# pic.net
KiCad netlist of a schematic drawn in Altium Designer
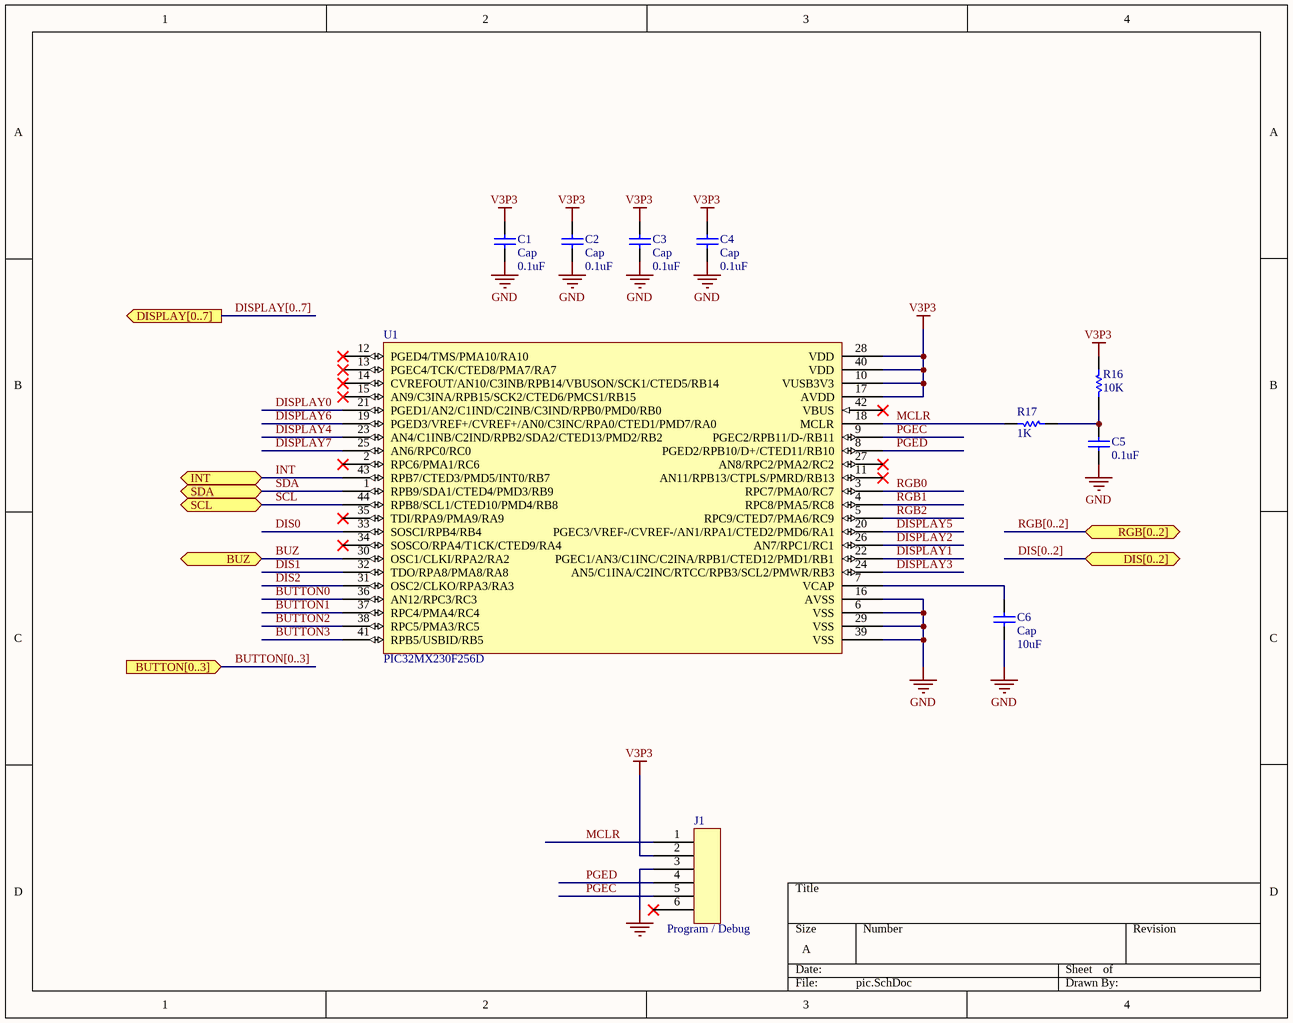
[diagram p0: pic.SchDoc]

(export (version "E")
  (design (tool "Eeschema 10.0.6"))
  (components
    (comp (ref "C1")
      (value "Cap")
      (footprint "Capacitor")
      (description "Capacitor")
      (fields (field (name "ALTIUM_VALUE") "0.1uF") (field (name "PUBLISHER") "Altium Limited"))
      (libsource (lib "libProject") (part "Capacitor"))
    )
    (comp (ref "C2")
      (value "Cap")
      (footprint "Capacitor")
      (description "Capacitor")
      (fields (field (name "ALTIUM_VALUE") "0.1uF") (field (name "PUBLISHER") "Altium Limited"))
      (libsource (lib "libProject") (part "Capacitor"))
    )
    (comp (ref "C3")
      (value "Cap")
      (footprint "Capacitor")
      (description "Capacitor")
      (fields (field (name "ALTIUM_VALUE") "0.1uF") (field (name "PUBLISHER") "Altium Limited"))
      (libsource (lib "libProject") (part "Capacitor"))
    )
    (comp (ref "C4")
      (value "Cap")
      (footprint "Capacitor")
      (description "Capacitor")
      (fields (field (name "ALTIUM_VALUE") "0.1uF") (field (name "PUBLISHER") "Altium Limited"))
      (libsource (lib "libProject") (part "Capacitor"))
    )
    (comp (ref "C5")
      (value "0.1uF")
      (footprint "Capacitor")
      (description "Capacitor")
      (fields (field (name "Comment") "Cap") (field (name "PUBLISHER") "Altium Limited"))
      (libsource (lib "libProject") (part "Capacitor"))
    )
    (comp (ref "C6")
      (value "Cap")
      (footprint "Capacitor")
      (description "Capacitor")
      (fields (field (name "ALTIUM_VALUE") "10uF") (field (name "PUBLISHER") "Altium Limited"))
      (libsource (lib "Miscellaneous Devices") (part "Cap"))
    )
    (comp (ref "J1") (value "Program / Debug") (footprint "ICSP") (libsource (lib "TP2") (part "CON6")))
    (comp (ref "R16")
      (value "10K")
      (footprint "RESISTANCE")
      (description "Resistor")
      (fields (field (name "PUBLISHER") "Altium Limited"))
      (libsource (lib "Miscellaneous Devices") (part "Res1"))
    )
    (comp (ref "R17")
      (value "1K")
      (footprint "RESISTANCE")
      (description "Resistor")
      (fields (field (name "Comment") "10K") (field (name "PUBLISHER") "Altium Limited"))
      (libsource (lib "Miscellaneous Devices") (part "Res1"))
    )
    (comp (ref "U1")
      (value "PIC32MX230F256D")
      (footprint "PIC32")
      (libsource (lib "libProject") (part "PIC32MX230F256D"))
    )
  )
  (nets
    (net (code "1") (name "/BUTTON0") (class "Default")
      (node (ref "U1") (pin "36") (pinfunction "AN12/RPC3/RC3_36") (pintype "bidirectional"))
    )
    (net (code "2") (name "/BUTTON1") (class "Default")
      (node (ref "U1") (pin "37") (pinfunction "RPC4/PMA4/RC4_37") (pintype "bidirectional"))
    )
    (net (code "3") (name "/BUTTON2") (class "Default")
      (node (ref "U1") (pin "38") (pinfunction "RPC5/PMA3/RC5_38") (pintype "bidirectional"))
    )
    (net (code "4") (name "/BUTTON3") (class "Default")
      (node (ref "U1") (pin "41") (pinfunction "RPB5/USBID/RB5_41") (pintype "bidirectional"))
    )
    (net (code "6") (name "/BUZ") (class "Default")
      (node (ref "U1") (pin "30") (pinfunction "OSC1/CLKI/RPA2/RA2_30") (pintype "bidirectional"))
    )
    (net (code "7") (name "/DIS0") (class "Default")
      (node (ref "U1") (pin "33") (pinfunction "SOSCI/RPB4/RB4_33") (pintype "bidirectional"))
    )
    (net (code "8") (name "/DIS1") (class "Default")
      (node (ref "U1") (pin "32") (pinfunction "TDO/RPA8/PMA8/RA8_32") (pintype "bidirectional"))
    )
    (net (code "9") (name "/DIS2") (class "Default")
      (node (ref "U1") (pin "31") (pinfunction "OSC2/CLKO/RPA3/RA3_31") (pintype "bidirectional"))
    )
    (net (code "10") (name "/DISPLAY0") (class "Default")
      (node (ref "U1") (pin "21") (pinfunction "PGED1/AN2/C1IND/C2INB/C3IND/RPB0/PMD0/RB0_21") (pintype "bidirectional"))
    )
    (net (code "11") (name "/DISPLAY1") (class "Default")
      (node (ref "U1") (pin "22") (pinfunction "PGEC1/AN3/C1INC/C2INA/RPB1/CTED12/PMD1/RB1_22") (pintype "bidirectional"))
    )
    (net (code "12") (name "/DISPLAY2") (class "Default")
      (node (ref "U1") (pin "26") (pinfunction "AN7/RPC1/RC1_26") (pintype "bidirectional"))
    )
    (net (code "13") (name "/DISPLAY3") (class "Default")
      (node (ref "U1") (pin "24") (pinfunction "AN5/C1INA/C2INC/RTCC/RPB3/SCL2/PMWR/RB3_24") (pintype "bidirectional"))
    )
    (net (code "14") (name "/DISPLAY4") (class "Default")
      (node (ref "U1") (pin "23") (pinfunction "AN4/C1INB/C2IND/RPB2/SDA2/CTED13/PMD2/RB2_23") (pintype "bidirectional"))
    )
    (net (code "15") (name "/DISPLAY5") (class "Default")
      (node (ref "U1") (pin "20") (pinfunction "PGEC3/VREF-/CVREF-/AN1/RPA1/CTED2/PMD6/RA1_20") (pintype "bidirectional"))
    )
    (net (code "16") (name "/DISPLAY6") (class "Default")
      (node (ref "U1") (pin "19") (pinfunction "PGED3/VREF+/CVREF+/AN0/C3INC/RPA0/CTED1/PMD7/RA0_19") (pintype "bidirectional"))
    )
    (net (code "17") (name "/DISPLAY7") (class "Default")
      (node (ref "U1") (pin "25") (pinfunction "AN6/RPC0/RC0_25") (pintype "bidirectional"))
    )
    (net (code "20") (name "/INT") (class "Default")
      (node (ref "U1") (pin "43") (pinfunction "RPB7/CTED3/PMD5/INT0/RB7_43") (pintype "bidirectional"))
    )
    (net (code "21") (name "/MCLR") (class "Default")
      (node (ref "J1") (pin "1") (pinfunction "1_1") (pintype "passive"))
      (node (ref "R17") (pin "1") (pinfunction "1_1") (pintype "passive"))
      (node (ref "U1") (pin "18") (pinfunction "MCLR_18") (pintype "power_in"))
    )
    (net (code "22") (name "/PGEC") (class "Default")
      (node (ref "J1") (pin "5") (pinfunction "5_5") (pintype "passive"))
      (node (ref "U1") (pin "9") (pinfunction "PGEC2/RPB11/D-/RB11_9") (pintype "bidirectional"))
    )
    (net (code "23") (name "/PGED") (class "Default")
      (node (ref "J1") (pin "4") (pinfunction "4_4") (pintype "passive"))
      (node (ref "U1") (pin "8") (pinfunction "PGED2/RPB10/D+/CTED11/RB10_8") (pintype "bidirectional"))
    )
    (net (code "24") (name "/RGB0") (class "Default")
      (node (ref "U1") (pin "3") (pinfunction "RPC7/PMA0/RC7_3") (pintype "bidirectional"))
    )
    (net (code "25") (name "/RGB1") (class "Default")
      (node (ref "U1") (pin "4") (pinfunction "RPC8/PMA5/RC8_4") (pintype "bidirectional"))
    )
    (net (code "26") (name "/RGB2") (class "Default")
      (node (ref "U1") (pin "5") (pinfunction "RPC9/CTED7/PMA6/RC9_5") (pintype "bidirectional"))
    )
    (net (code "28") (name "/SCL") (class "Default")
      (node (ref "U1") (pin "44") (pinfunction "RPB8/SCL1/CTED10/PMD4/RB8_44") (pintype "bidirectional"))
    )
    (net (code "29") (name "/SDA") (class "Default")
      (node (ref "U1") (pin "1") (pinfunction "RPB9/SDA1/CTED4/PMD3/RB9_1") (pintype "bidirectional"))
    )
    (net (code "30") (name "GND") (class "Default")
      (node (ref "C1") (pin "1") (pinfunction "1_1") (pintype "passive"))
      (node (ref "C2") (pin "1") (pinfunction "1_1") (pintype "passive"))
      (node (ref "C3") (pin "1") (pinfunction "1_1") (pintype "passive"))
      (node (ref "C4") (pin "1") (pinfunction "1_1") (pintype "passive"))
      (node (ref "C5") (pin "1") (pinfunction "1_1") (pintype "passive"))
      (node (ref "C6") (pin "1") (pinfunction "1_1") (pintype "passive"))
      (node (ref "J1") (pin "3") (pinfunction "3_3") (pintype "passive"))
      (node (ref "U1") (pin "16") (pinfunction "AVSS_16") (pintype "power_in"))
      (node (ref "U1") (pin "29") (pinfunction "VSS_29") (pintype "power_in"))
      (node (ref "U1") (pin "39") (pinfunction "VSS_39") (pintype "power_in"))
      (node (ref "U1") (pin "6") (pinfunction "VSS_6") (pintype "power_in"))
    )
    (net (code "31") (name "Net-(C5-Pad2)") (class "Default")
      (node (ref "C5") (pin "2") (pinfunction "2_2") (pintype "passive"))
      (node (ref "R16") (pin "1") (pinfunction "1_1") (pintype "passive"))
      (node (ref "R17") (pin "2") (pinfunction "2_2") (pintype "passive"))
    )
    (net (code "32") (name "Net-(U1-VCAP)") (class "Default")
      (node (ref "C6") (pin "2") (pinfunction "2_2") (pintype "passive"))
      (node (ref "U1") (pin "7") (pinfunction "VCAP_7") (pintype "power_in"))
    )
    (net (code "33") (name "V3P3") (class "Default")
      (node (ref "C1") (pin "2") (pinfunction "2_2") (pintype "passive"))
      (node (ref "C2") (pin "2") (pinfunction "2_2") (pintype "passive"))
      (node (ref "C3") (pin "2") (pinfunction "2_2") (pintype "passive"))
      (node (ref "C4") (pin "2") (pinfunction "2_2") (pintype "passive"))
      (node (ref "J1") (pin "2") (pinfunction "2_2") (pintype "passive"))
      (node (ref "R16") (pin "2") (pinfunction "2_2") (pintype "passive"))
      (node (ref "U1") (pin "10") (pinfunction "VUSB3V3_10") (pintype "power_in"))
      (node (ref "U1") (pin "17") (pinfunction "AVDD_17") (pintype "power_in"))
      (node (ref "U1") (pin "28") (pinfunction "VDD_28") (pintype "power_in"))
      (node (ref "U1") (pin "40") (pinfunction "VDD_40") (pintype "power_in"))
    )
    (net (code "34") (name "unconnected-(J1-Pad6)") (class "Default")
      (node (ref "J1") (pin "6") (pinfunction "6_6") (pintype "passive+no_connect"))
    )
    (net (code "35") (name "unconnected-(U1-AN8{slash}RPC2{slash}PMA2{slash}RC2-Pad27)") (class "Default")
      (node (ref "U1") (pin "27") (pinfunction "AN8/RPC2/PMA2/RC2_27") (pintype "bidirectional+no_connect"))
    )
    (net (code "36") (name "unconnected-(U1-AN9{slash}C3INA{slash}RPB15{slash}SCK2{slash}CTED6{slash}PMCS1{slash}RB15-Pad15)") (class "Default")
      (node (ref "U1") (pin "15") (pinfunction "AN9/C3INA/RPB15/SCK2/CTED6/PMCS1/RB15_15") (pintype "bidirectional+no_connect"))
    )
    (net (code "37") (name "unconnected-(U1-AN11{slash}RPB13{slash}CTPLS{slash}PMRD{slash}RB13-Pad11)") (class "Default")
      (node (ref "U1") (pin "11") (pinfunction "AN11/RPB13/CTPLS/PMRD/RB13_11") (pintype "bidirectional+no_connect"))
    )
    (net (code "38") (name "unconnected-(U1-CVREFOUT{slash}AN10{slash}C3INB{slash}RPB14{slash}VBUSON{slash}SCK1{slash}CTED5{slash}RB14-Pad14)") (class "Default")
      (node (ref "U1") (pin "14") (pinfunction "CVREFOUT/AN10/C3INB/RPB14/VBUSON/SCK1/CTED5/RB14_14") (pintype "bidirectional+no_connect"))
    )
    (net (code "39") (name "unconnected-(U1-PGEC4{slash}TCK{slash}CTED8{slash}PMA7{slash}RA7-Pad13)") (class "Default")
      (node (ref "U1") (pin "13") (pinfunction "PGEC4/TCK/CTED8/PMA7/RA7_13") (pintype "bidirectional+no_connect"))
    )
    (net (code "40") (name "unconnected-(U1-PGED4{slash}TMS{slash}PMA10{slash}RA10-Pad12)") (class "Default")
      (node (ref "U1") (pin "12") (pinfunction "PGED4/TMS/PMA10/RA10_12") (pintype "bidirectional+no_connect"))
    )
    (net (code "41") (name "unconnected-(U1-RPC6{slash}PMA1{slash}RC6-Pad2)") (class "Default")
      (node (ref "U1") (pin "2") (pinfunction "RPC6/PMA1/RC6_2") (pintype "bidirectional+no_connect"))
    )
    (net (code "42") (name "unconnected-(U1-SOSCO{slash}RPA4{slash}T1CK{slash}CTED9{slash}RA4-Pad34)") (class "Default")
      (node (ref "U1") (pin "34") (pinfunction "SOSCO/RPA4/T1CK/CTED9/RA4_34") (pintype "bidirectional+no_connect"))
    )
    (net (code "43") (name "unconnected-(U1-TDI{slash}RPA9{slash}PMA9{slash}RA9-Pad35)") (class "Default")
      (node (ref "U1") (pin "35") (pinfunction "TDI/RPA9/PMA9/RA9_35") (pintype "bidirectional+no_connect"))
    )
    (net (code "44") (name "unconnected-(U1-VBUS-Pad42)") (class "Default")
      (node (ref "U1") (pin "42") (pinfunction "VBUS_42") (pintype "input+no_connect"))
    )
  )
)
